# DE10-STD-ADC-Sch.net
KiCad netlist of a schematic drawn in EAGLE
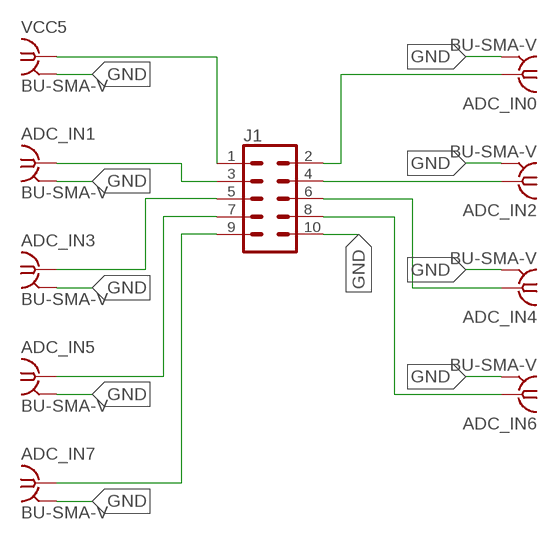
[diagram p0: schematic, sheet 1]

(export (version "E")
  (design (tool "Eeschema 10.0.6"))
  (components
    (comp (ref "ADC_IN0")
      (value "BU-SMA-V")
      (footprint "eagle-import:BU-SMA-V")
      (libsource (lib "eagle-import") (part "BU-SMA-V"))
    )
    (comp (ref "ADC_IN1")
      (value "BU-SMA-V")
      (footprint "eagle-import:BU-SMA-V")
      (libsource (lib "eagle-import") (part "BU-SMA-V"))
    )
    (comp (ref "ADC_IN2")
      (value "BU-SMA-V")
      (footprint "eagle-import:BU-SMA-V")
      (libsource (lib "eagle-import") (part "BU-SMA-V"))
    )
    (comp (ref "ADC_IN3")
      (value "BU-SMA-V")
      (footprint "eagle-import:BU-SMA-V")
      (libsource (lib "eagle-import") (part "BU-SMA-V"))
    )
    (comp (ref "ADC_IN4")
      (value "BU-SMA-V")
      (footprint "eagle-import:BU-SMA-V")
      (libsource (lib "eagle-import") (part "BU-SMA-V"))
    )
    (comp (ref "ADC_IN5")
      (value "BU-SMA-V")
      (footprint "eagle-import:BU-SMA-V")
      (libsource (lib "eagle-import") (part "BU-SMA-V"))
    )
    (comp (ref "ADC_IN6")
      (value "BU-SMA-V")
      (footprint "eagle-import:BU-SMA-V")
      (libsource (lib "eagle-import") (part "BU-SMA-V"))
    )
    (comp (ref "ADC_IN7")
      (value "BU-SMA-V")
      (footprint "eagle-import:BU-SMA-V")
      (libsource (lib "eagle-import") (part "BU-SMA-V"))
    )
    (comp (ref "J1")
      (value "CONN_05X2SHD-NS")
      (footprint "eagle-import:2X5-SHROUDED-NS")
      (libsource (lib "eagle-import") (part "CONN_05X2SHD-NS"))
    )
    (comp (ref "VCC5")
      (value "BU-SMA-V")
      (footprint "eagle-import:BU-SMA-V")
      (libsource (lib "eagle-import") (part "BU-SMA-V"))
    )
  )
  (nets
    (net (code "1") (name "GND") (class "Default")
      (node (ref "ADC_IN0") (pin "2") (pinfunction "2_2") (pintype "passive"))
      (node (ref "ADC_IN0") (pin "3") (pinfunction "2_3") (pintype "passive"))
      (node (ref "ADC_IN0") (pin "4") (pinfunction "2_4") (pintype "passive"))
      (node (ref "ADC_IN0") (pin "5") (pinfunction "2_5") (pintype "passive"))
      (node (ref "ADC_IN1") (pin "2") (pinfunction "2_2") (pintype "passive"))
      (node (ref "ADC_IN1") (pin "3") (pinfunction "2_3") (pintype "passive"))
      (node (ref "ADC_IN1") (pin "4") (pinfunction "2_4") (pintype "passive"))
      (node (ref "ADC_IN1") (pin "5") (pinfunction "2_5") (pintype "passive"))
      (node (ref "ADC_IN2") (pin "2") (pinfunction "2_2") (pintype "passive"))
      (node (ref "ADC_IN2") (pin "3") (pinfunction "2_3") (pintype "passive"))
      (node (ref "ADC_IN2") (pin "4") (pinfunction "2_4") (pintype "passive"))
      (node (ref "ADC_IN2") (pin "5") (pinfunction "2_5") (pintype "passive"))
      (node (ref "ADC_IN3") (pin "2") (pinfunction "2_2") (pintype "passive"))
      (node (ref "ADC_IN3") (pin "3") (pinfunction "2_3") (pintype "passive"))
      (node (ref "ADC_IN3") (pin "4") (pinfunction "2_4") (pintype "passive"))
      (node (ref "ADC_IN3") (pin "5") (pinfunction "2_5") (pintype "passive"))
      (node (ref "ADC_IN4") (pin "2") (pinfunction "2_2") (pintype "passive"))
      (node (ref "ADC_IN4") (pin "3") (pinfunction "2_3") (pintype "passive"))
      (node (ref "ADC_IN4") (pin "4") (pinfunction "2_4") (pintype "passive"))
      (node (ref "ADC_IN4") (pin "5") (pinfunction "2_5") (pintype "passive"))
      (node (ref "ADC_IN5") (pin "2") (pinfunction "2_2") (pintype "passive"))
      (node (ref "ADC_IN5") (pin "3") (pinfunction "2_3") (pintype "passive"))
      (node (ref "ADC_IN5") (pin "4") (pinfunction "2_4") (pintype "passive"))
      (node (ref "ADC_IN5") (pin "5") (pinfunction "2_5") (pintype "passive"))
      (node (ref "ADC_IN6") (pin "2") (pinfunction "2_2") (pintype "passive"))
      (node (ref "ADC_IN6") (pin "3") (pinfunction "2_3") (pintype "passive"))
      (node (ref "ADC_IN6") (pin "4") (pinfunction "2_4") (pintype "passive"))
      (node (ref "ADC_IN6") (pin "5") (pinfunction "2_5") (pintype "passive"))
      (node (ref "ADC_IN7") (pin "2") (pinfunction "2_2") (pintype "passive"))
      (node (ref "ADC_IN7") (pin "3") (pinfunction "2_3") (pintype "passive"))
      (node (ref "ADC_IN7") (pin "4") (pinfunction "2_4") (pintype "passive"))
      (node (ref "ADC_IN7") (pin "5") (pinfunction "2_5") (pintype "passive"))
      (node (ref "J1") (pin "10") (pinfunction "10_10") (pintype "passive"))
      (node (ref "VCC5") (pin "2") (pinfunction "2_2") (pintype "passive"))
      (node (ref "VCC5") (pin "3") (pinfunction "2_3") (pintype "passive"))
      (node (ref "VCC5") (pin "4") (pinfunction "2_4") (pintype "passive"))
      (node (ref "VCC5") (pin "5") (pinfunction "2_5") (pintype "passive"))
    )
    (net (code "2") (name "Net-(ADC_IN0-Pad1)") (class "Default")
      (node (ref "ADC_IN0") (pin "1") (pinfunction "1_1") (pintype "passive"))
      (node (ref "J1") (pin "2") (pinfunction "2_2") (pintype "passive"))
    )
    (net (code "3") (name "Net-(ADC_IN1-Pad1)") (class "Default")
      (node (ref "ADC_IN1") (pin "1") (pinfunction "1_1") (pintype "passive"))
      (node (ref "J1") (pin "3") (pinfunction "3_3") (pintype "passive"))
    )
    (net (code "4") (name "Net-(ADC_IN2-Pad1)") (class "Default")
      (node (ref "ADC_IN2") (pin "1") (pinfunction "1_1") (pintype "passive"))
      (node (ref "J1") (pin "4") (pinfunction "4_4") (pintype "passive"))
    )
    (net (code "5") (name "Net-(ADC_IN3-Pad1)") (class "Default")
      (node (ref "ADC_IN3") (pin "1") (pinfunction "1_1") (pintype "passive"))
      (node (ref "J1") (pin "5") (pinfunction "5_5") (pintype "passive"))
    )
    (net (code "6") (name "Net-(ADC_IN4-Pad1)") (class "Default")
      (node (ref "ADC_IN4") (pin "1") (pinfunction "1_1") (pintype "passive"))
      (node (ref "J1") (pin "6") (pinfunction "6_6") (pintype "passive"))
    )
    (net (code "7") (name "Net-(ADC_IN5-Pad1)") (class "Default")
      (node (ref "ADC_IN5") (pin "1") (pinfunction "1_1") (pintype "passive"))
      (node (ref "J1") (pin "7") (pinfunction "7_7") (pintype "passive"))
    )
    (net (code "8") (name "Net-(ADC_IN6-Pad1)") (class "Default")
      (node (ref "ADC_IN6") (pin "1") (pinfunction "1_1") (pintype "passive"))
      (node (ref "J1") (pin "8") (pinfunction "8_8") (pintype "passive"))
    )
    (net (code "9") (name "Net-(ADC_IN7-Pad1)") (class "Default")
      (node (ref "ADC_IN7") (pin "1") (pinfunction "1_1") (pintype "passive"))
      (node (ref "J1") (pin "9") (pinfunction "9_9") (pintype "passive"))
    )
    (net (code "10") (name "Net-(J1-Pad1)") (class "Default")
      (node (ref "J1") (pin "1") (pinfunction "1_1") (pintype "passive"))
      (node (ref "VCC5") (pin "1") (pinfunction "1_1") (pintype "passive"))
    )
  )
)
